# test.net
KiCad netlist of a schematic drawn in EAGLE
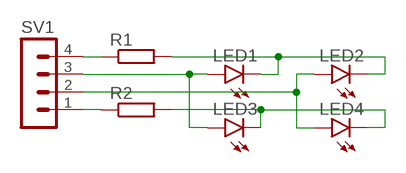
[diagram p0: schematic, sheet 1]

(export (version "E")
  (design (tool "Eeschema 10.0.6"))
  (components
    (comp (ref "LED1")
      (value "LEDCHIPLED_1206")
      (footprint "eagle-import:CHIPLED_1206")
      (libsource (lib "eagle-import") (part "LEDCHIPLED_1206"))
    )
    (comp (ref "LED2")
      (value "LEDCHIPLED_1206")
      (footprint "eagle-import:CHIPLED_1206")
      (libsource (lib "eagle-import") (part "LEDCHIPLED_1206"))
    )
    (comp (ref "LED3")
      (value "LEDCHIPLED_1206")
      (footprint "eagle-import:CHIPLED_1206")
      (libsource (lib "eagle-import") (part "LEDCHIPLED_1206"))
    )
    (comp (ref "LED4")
      (value "LEDCHIPLED_1206")
      (footprint "eagle-import:CHIPLED_1206")
      (libsource (lib "eagle-import") (part "LEDCHIPLED_1206"))
    )
    (comp (ref "R1")
      (value "R-EU_M1206")
      (footprint "eagle-import:M1206")
      (libsource (lib "eagle-import") (part "R-EU_M1206"))
    )
    (comp (ref "R2")
      (value "R-EU_M1206")
      (footprint "eagle-import:M1206")
      (libsource (lib "eagle-import") (part "R-EU_M1206"))
    )
    (comp (ref "SV1")
      (value "MA04-1")
      (footprint "eagle-import:MA04-1")
      (libsource (lib "eagle-import") (part "MA04-1"))
    )
  )
  (nets
    (net (code "1") (name "Net-(LED1-PadA)") (class "Default")
      (node (ref "LED1") (pin "A") (pinfunction "A_A") (pintype "passive"))
      (node (ref "LED3") (pin "A") (pinfunction "A_A") (pintype "passive"))
      (node (ref "SV1") (pin "3") (pinfunction "3_3") (pintype "passive"))
    )
    (net (code "2") (name "Net-(LED1-PadC)") (class "Default")
      (node (ref "LED1") (pin "C") (pinfunction "C_C") (pintype "passive"))
      (node (ref "LED2") (pin "C") (pinfunction "C_C") (pintype "passive"))
      (node (ref "R1") (pin "2") (pinfunction "2_2") (pintype "passive"))
    )
    (net (code "3") (name "Net-(LED2-PadA)") (class "Default")
      (node (ref "LED2") (pin "A") (pinfunction "A_A") (pintype "passive"))
      (node (ref "LED4") (pin "A") (pinfunction "A_A") (pintype "passive"))
      (node (ref "SV1") (pin "2") (pinfunction "2_2") (pintype "passive"))
    )
    (net (code "4") (name "Net-(LED3-PadC)") (class "Default")
      (node (ref "LED3") (pin "C") (pinfunction "C_C") (pintype "passive"))
      (node (ref "LED4") (pin "C") (pinfunction "C_C") (pintype "passive"))
      (node (ref "R2") (pin "2") (pinfunction "2_2") (pintype "passive"))
    )
    (net (code "5") (name "Net-(R1-Pad1)") (class "Default")
      (node (ref "R1") (pin "1") (pinfunction "1_1") (pintype "passive"))
      (node (ref "SV1") (pin "4") (pinfunction "4_4") (pintype "passive"))
    )
    (net (code "6") (name "Net-(R2-Pad1)") (class "Default")
      (node (ref "R2") (pin "1") (pinfunction "1_1") (pintype "passive"))
      (node (ref "SV1") (pin "1") (pinfunction "1_1") (pintype "passive"))
    )
  )
)
